# Communication.net
KiCad netlist of a schematic drawn in Altium Designer
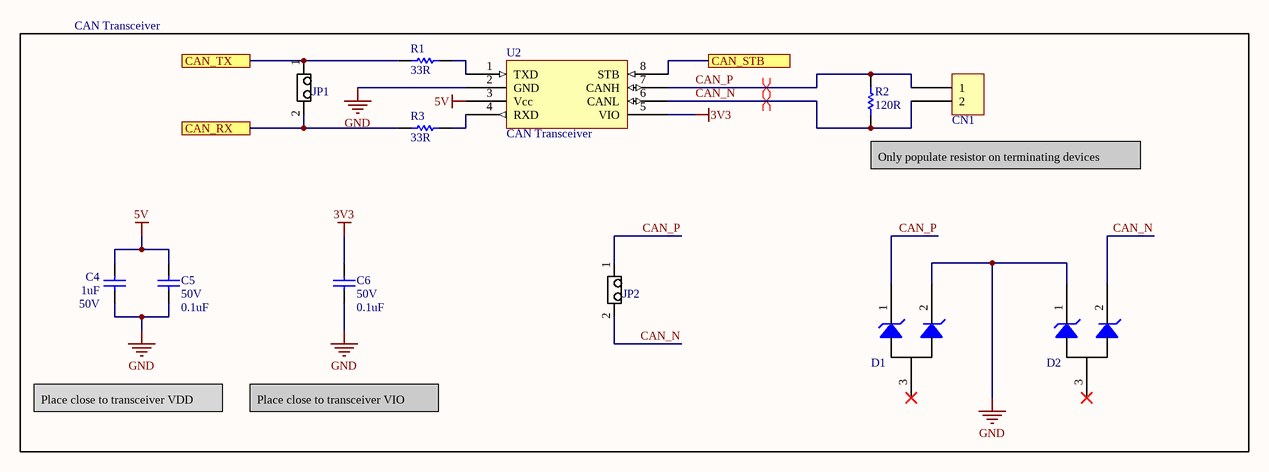
[diagram p0: Communication.SchDoc]

(export (version "E")
  (design (tool "Eeschema 10.0.6"))
  (components
    (comp (ref "C4")
      (value "CL21B105KBFNNNG")
      (footprint "0803 CAP")
      (description "SAMSUNG ELECTRO-MECHANICS - CL21B105KBFNNNG - MLCC CAPACITORS")
      (fields
        (field (name "CAPACITANCE") "1uF")
        (field (name "TOLERANCE") "10%")
        (field (name "VOLTAGE") "50V")
      )
      (libsource (lib "AUVIC") (part "Symbol"))
    )
    (comp (ref "C5")
      (value "CL10B104JB8NNNC")
      (footprint "FP-CL10-0_1-IPC_A")
      (description "CAP CER 0.1UF 50V X7R 0603")
      (fields
        (field (name "TOLERANCE") "5%")
        (field (name "VOLTAGE") "50V")
        (field (name "CAPACITANCE") "0.1uF")
      )
      (libsource (lib "AUVIC") (part "CAP-NP-2"))
    )
    (comp (ref "C6")
      (value "CL10B104JB8NNNC")
      (footprint "FP-CL10-0_1-IPC_A")
      (description "CAP CER 0.1UF 50V X7R 0603")
      (fields
        (field (name "TOLERANCE") "5%")
        (field (name "VOLTAGE") "50V")
        (field (name "CAPACITANCE") "0.1uF")
      )
      (libsource (lib "AUVIC") (part "CAP-NP-2"))
    )
    (comp (ref "CN1")
      (value "1x2 Shrouded Right Angle")
      (footprint "2X1 Female Header")
      (description "02 MTE HDR SRRA LATCH")
      (libsource (lib "AUVIC") (part "1x2 Shrouded Right Angle"))
    )
    (comp (ref "D1")
      (value "PESD36VS2UT,215")
      (footprint "SOT95P245X110-3N")
      (description "TVS DIODE 36V 60V SOT23")
      (fields (field (name "CREATED BY") "Miguel Manguerra"))
      (libsource (lib "AUVIC") (part "PESD36VS2UT,215"))
    )
    (comp (ref "D2")
      (value "PESD36VS2UT,215")
      (footprint "SOT95P245X110-3N")
      (description "TVS DIODE 36V 60V SOT23")
      (fields (field (name "CREATED BY") "Miguel Manguerra"))
      (libsource (lib "AUVIC") (part "PESD36VS2UT,215"))
    )
    (comp (ref "JP1")
      (value "1x2 Male Header")
      (footprint "2X1 Males Header")
      (fields (field (name "MADE BY") "Andy Bates"))
      (libsource (lib "AUVIC") (part "1x2 Male Header"))
    )
    (comp (ref "JP2")
      (value "1x2 Male Header")
      (footprint "2X1 Males Header")
      (fields (field (name "MADE BY") "Andy Bates"))
      (libsource (lib "AUVIC") (part "1x2 Male Header"))
    )
    (comp (ref "R1")
      (value "RC0603FR-0733RL")
      (footprint "RESC1608X55X25LL10T15")
      (description "Res Thick Film 0603 33 Ohm 1% 1/10W +/-100ppm/ßC Molded SMD Paper T/R")
      (fields (field (name "RESISTANCE") "33R") (field (name "TOLERANCE") "1%"))
      (libsource (lib "AUVIC") (part "RES-2"))
    )
    (comp (ref "R2")
      (value "RC0603FR-07120RL")
      (footprint "RESC1608X55X25LL10T15")
      (description "Res Thick Film 0603 120 Ohm 1% 0.1W(1/10W) ±100ppm/C Epoxy SMD T/R")
      (fields (field (name "RESISTANCE") "120R") (field (name "TOLERANCE") "1%"))
      (libsource (lib "AUVIC") (part "RES-2"))
    )
    (comp (ref "R3")
      (value "RC0603FR-0733RL")
      (footprint "RESC1608X55X25LL10T15")
      (description "Res Thick Film 0603 33 Ohm 1% 1/10W +/-100ppm/ßC Molded SMD Paper T/R")
      (fields (field (name "RESISTANCE") "33R") (field (name "TOLERANCE") "1%"))
      (libsource (lib "AUVIC") (part "RES-2"))
    )
    (comp (ref "U2")
      (value "CAN Transceiver")
      (footprint "8-SOIC")
      (description "1/1 Transceiver Half CANbus 8-SO")
      (libsource (lib "AUVIC") (part "CAN Transceiver"))
    )
  )
  (nets
    (net (code "1") (name "/CAN_N") (class "Default")
      (node (ref "CN1") (pin "2") (pinfunction "2_2") (pintype "passive"))
      (node (ref "D2") (pin "2") (pinfunction "Cathode_2_2") (pintype "passive"))
      (node (ref "JP2") (pin "2") (pinfunction "2_2") (pintype "passive"))
      (node (ref "R2") (pin "1") (pinfunction "1_1") (pintype "passive"))
      (node (ref "U2") (pin "6") (pinfunction "CANL_6") (pintype "bidirectional"))
    )
    (net (code "2") (name "/CAN_P") (class "Default")
      (node (ref "CN1") (pin "1") (pinfunction "1_1") (pintype "passive"))
      (node (ref "D1") (pin "1") (pinfunction "Cathode_1_1") (pintype "passive"))
      (node (ref "JP2") (pin "1") (pinfunction "1_1") (pintype "passive"))
      (node (ref "R2") (pin "2") (pinfunction "2_2") (pintype "passive"))
      (node (ref "U2") (pin "7") (pinfunction "CANH_7") (pintype "bidirectional"))
    )
    (net (code "3") (name "/CAN_RX") (class "Default")
      (node (ref "JP1") (pin "2") (pinfunction "2_2") (pintype "passive"))
      (node (ref "R3") (pin "1") (pinfunction "1_1") (pintype "passive"))
    )
    (net (code "4") (name "/CAN_STB") (class "Default")
      (node (ref "U2") (pin "8") (pinfunction "STB_8") (pintype "input"))
    )
    (net (code "5") (name "/CAN_TX") (class "Default")
      (node (ref "JP1") (pin "1") (pinfunction "1_1") (pintype "passive"))
      (node (ref "R1") (pin "1") (pinfunction "1_1") (pintype "passive"))
    )
    (net (code "6") (name "3V3") (class "Default")
      (node (ref "C6") (pin "2") (pinfunction "2_2") (pintype "passive"))
      (node (ref "U2") (pin "5") (pinfunction "VIO_5") (pintype "passive"))
    )
    (net (code "7") (name "5V") (class "Default")
      (node (ref "C4") (pin "2") (pinfunction "2_2") (pintype "passive"))
      (node (ref "C5") (pin "2") (pinfunction "2_2") (pintype "passive"))
      (node (ref "U2") (pin "3") (pinfunction "Vcc_3") (pintype "power_in"))
    )
    (net (code "8") (name "GND") (class "Default")
      (node (ref "C4") (pin "1") (pinfunction "1_1") (pintype "passive"))
      (node (ref "C5") (pin "1") (pinfunction "1_1") (pintype "passive"))
      (node (ref "C6") (pin "1") (pinfunction "1_1") (pintype "passive"))
      (node (ref "D1") (pin "2") (pinfunction "Cathode_2_2") (pintype "passive"))
      (node (ref "D2") (pin "1") (pinfunction "Cathode_1_1") (pintype "passive"))
      (node (ref "U2") (pin "2") (pinfunction "GND_2") (pintype "power_in"))
    )
    (net (code "9") (name "Net-(U2-RXD)") (class "Default")
      (node (ref "R3") (pin "2") (pinfunction "2_2") (pintype "passive"))
      (node (ref "U2") (pin "4") (pinfunction "RXD_4") (pintype "output"))
    )
    (net (code "10") (name "Net-(U2-TXD)") (class "Default")
      (node (ref "R1") (pin "2") (pinfunction "2_2") (pintype "passive"))
      (node (ref "U2") (pin "1") (pinfunction "TXD_1") (pintype "input"))
    )
    (net (code "11") (name "unconnected-(D1-Common_Anode-Pad3)") (class "Default")
      (node (ref "D1") (pin "3") (pinfunction "Common_Anode_3") (pintype "passive"))
    )
    (net (code "12") (name "unconnected-(D2-Common_Anode-Pad3)") (class "Default")
      (node (ref "D2") (pin "3") (pinfunction "Common_Anode_3") (pintype "passive"))
    )
  )
)
